# display_dvd_connectors.net
KiCad netlist of a schematic drawn in Altium Designer
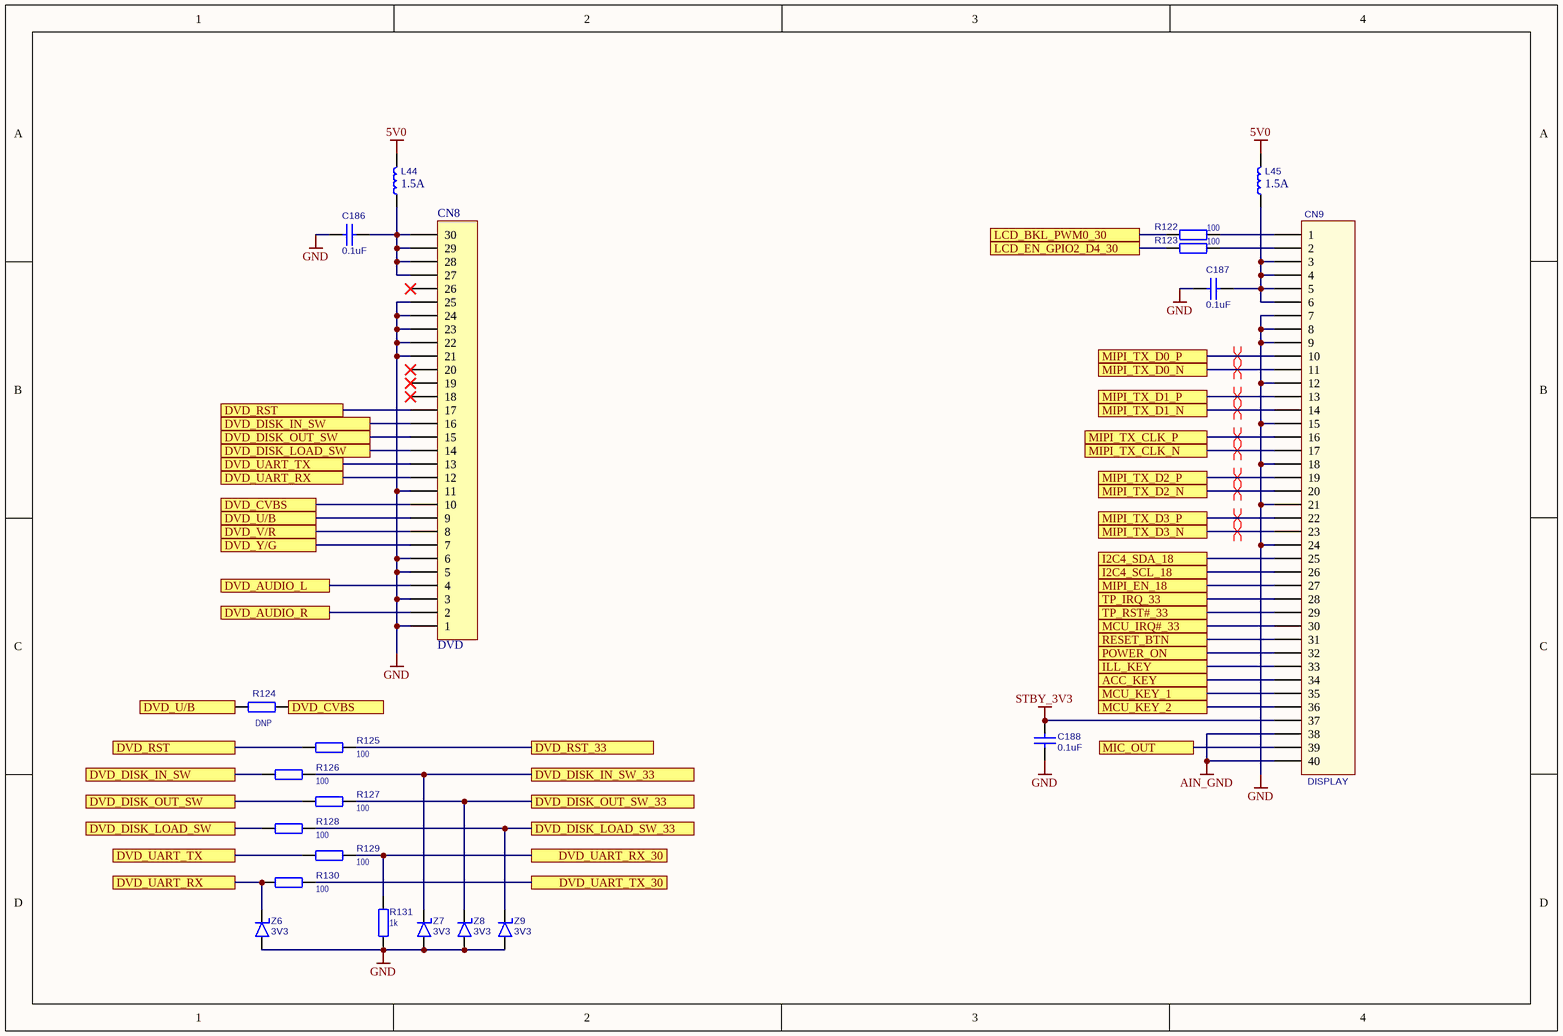
[diagram p0: display_dvd_connectors.SchDoc]

(export (version "E")
  (design (tool "Eeschema 10.0.6"))
  (components
    (comp (ref "C186")
      (value "0.1uF")
      (footprint "Capacitors:C0603")
      (description "CAP_NPOL")
      (fields (field (name "Comment") "C1608X7R1H104K080AA"))
      (libsource (lib "capacitors") (part "CAP_NPOL"))
    )
    (comp (ref "C187")
      (value "0.1uF")
      (footprint "Capacitors:C0603")
      (description "CAP_NPOL")
      (fields (field (name "Comment") "C1608X7R1H104K080AA"))
      (libsource (lib "capacitors") (part "CAP_NPOL"))
    )
    (comp (ref "C188")
      (value "0.1uF")
      (footprint "Capacitors:C0603")
      (description "CAP_NPOL")
      (fields (field (name "Comment") "C1608X7R1H104K080AA"))
      (libsource (lib "capacitors") (part "CAP_NPOL"))
    )
    (comp (ref "CN8")
      (value "DVD")
      (footprint "30S-0.5SH")
      (description "Header, 30-Pin")
      (fields (field (name "PUBLISHER") "Altium Limited"))
      (libsource (lib "HDR") (part "HDR 30"))
    )
    (comp (ref "CN9")
      (value "DISPLAY")
      (footprint "40S-0.5SH")
      (description "DT38")
      (libsource (lib "FPC_FH12-40S-0.5SH") (part "FH12-40"))
    )
    (comp (ref "L44")
      (value "1.5A")
      (footprint "IND1206")
      (description "IND_WO_IRON")
      (fields (field (name "Comment") "BLM31PG601SN1L"))
      (libsource (lib "inductors") (part "IND_WO_IRON"))
    )
    (comp (ref "L45")
      (value "1.5A")
      (footprint "IND1206")
      (description "IND_WO_IRON")
      (fields (field (name "Comment") "BLM31PG601SN1L"))
      (libsource (lib "inductors") (part "IND_WO_IRON"))
    )
    (comp (ref "R122")
      (value "100")
      (footprint "R0603")
      (description "RES")
      (libsource (lib "resistors") (part "RESISTOR"))
    )
    (comp (ref "R123")
      (value "100")
      (footprint "R0603")
      (description "RES")
      (libsource (lib "resistors") (part "RESISTOR"))
    )
    (comp (ref "R124")
      (value "DNP")
      (footprint "R0603")
      (description "RES")
      (libsource (lib "resistors") (part "RESISTOR"))
    )
    (comp (ref "R125")
      (value "100")
      (footprint "R0603")
      (description "RES")
      (libsource (lib "resistors") (part "RESISTOR"))
    )
    (comp (ref "R126")
      (value "100")
      (footprint "R0603")
      (description "RES")
      (libsource (lib "resistors") (part "RESISTOR"))
    )
    (comp (ref "R127")
      (value "100")
      (footprint "R0603")
      (description "RES")
      (libsource (lib "resistors") (part "RESISTOR"))
    )
    (comp (ref "R128")
      (value "100")
      (footprint "R0603")
      (description "RES")
      (libsource (lib "resistors") (part "RESISTOR"))
    )
    (comp (ref "R129")
      (value "100")
      (footprint "R0603")
      (description "RES")
      (libsource (lib "resistors") (part "RESISTOR"))
    )
    (comp (ref "R130")
      (value "100")
      (footprint "R0603")
      (description "RES")
      (libsource (lib "resistors") (part "RESISTOR"))
    )
    (comp (ref "R131")
      (value "1k")
      (footprint "R0603")
      (description "RES")
      (libsource (lib "resistors") (part "RESISTOR"))
    )
    (comp (ref "Z6")
      (value "3V3")
      (footprint "SOD-323")
      (description "ZENNER")
      (fields (field (name "Comment") "BZX384-C3V3.115"))
      (libsource (lib "diodes") (part "ZENNER_1"))
    )
    (comp (ref "Z7")
      (value "3V3")
      (footprint "SOD-323")
      (description "ZENNER")
      (fields (field (name "Comment") "BZX384-C3V3.115"))
      (libsource (lib "diodes") (part "ZENNER_1"))
    )
    (comp (ref "Z8")
      (value "3V3")
      (footprint "SOD-323")
      (description "ZENNER")
      (fields (field (name "Comment") "BZX384-C3V3.115"))
      (libsource (lib "diodes") (part "ZENNER_1"))
    )
    (comp (ref "Z9")
      (value "3V3")
      (footprint "SOD-323")
      (description "ZENNER")
      (fields (field (name "Comment") "BZX384-C3V3.115"))
      (libsource (lib "diodes") (part "ZENNER_1"))
    )
  )
  (nets
    (net (code "1") (name "/ACC_KEY") (class "Default")
      (node (ref "CN9") (pin "34") (pinfunction "34_34") (pintype "passive"))
    )
    (net (code "2") (name "/DVD_AUDIO_L") (class "Default")
      (node (ref "CN8") (pin "4") (pinfunction "4_4") (pintype "passive"))
    )
    (net (code "3") (name "/DVD_AUDIO_R") (class "Default")
      (node (ref "CN8") (pin "2") (pinfunction "2_2") (pintype "passive"))
    )
    (net (code "4") (name "/DVD_CVBS") (class "Default")
      (node (ref "CN8") (pin "10") (pinfunction "10_10") (pintype "passive"))
      (node (ref "R124") (pin "1") (pinfunction "1_1") (pintype "passive"))
    )
    (net (code "5") (name "/DVD_DISK_IN_SW") (class "Default")
      (node (ref "CN8") (pin "16") (pinfunction "16_16") (pintype "passive"))
      (node (ref "R126") (pin "2") (pinfunction "2_2") (pintype "passive"))
    )
    (net (code "6") (name "/DVD_DISK_IN_SW_33") (class "Default")
      (node (ref "R126") (pin "1") (pinfunction "1_1") (pintype "passive"))
      (node (ref "Z7") (pin "2") (pinfunction "K_2") (pintype "passive"))
    )
    (net (code "7") (name "/DVD_DISK_LOAD_SW") (class "Default")
      (node (ref "CN8") (pin "14") (pinfunction "14_14") (pintype "passive"))
      (node (ref "R128") (pin "2") (pinfunction "2_2") (pintype "passive"))
    )
    (net (code "8") (name "/DVD_DISK_LOAD_SW_33") (class "Default")
      (node (ref "R128") (pin "1") (pinfunction "1_1") (pintype "passive"))
      (node (ref "Z9") (pin "2") (pinfunction "K_2") (pintype "passive"))
    )
    (net (code "9") (name "/DVD_DISK_OUT_SW") (class "Default")
      (node (ref "CN8") (pin "15") (pinfunction "15_15") (pintype "passive"))
      (node (ref "R127") (pin "2") (pinfunction "2_2") (pintype "passive"))
    )
    (net (code "10") (name "/DVD_DISK_OUT_SW_33") (class "Default")
      (node (ref "R127") (pin "1") (pinfunction "1_1") (pintype "passive"))
      (node (ref "Z8") (pin "2") (pinfunction "K_2") (pintype "passive"))
    )
    (net (code "11") (name "/DVD_RST") (class "Default")
      (node (ref "CN8") (pin "17") (pinfunction "17_17") (pintype "passive"))
      (node (ref "R125") (pin "2") (pinfunction "2_2") (pintype "passive"))
    )
    (net (code "12") (name "/DVD_RST_33") (class "Default")
      (node (ref "R125") (pin "1") (pinfunction "1_1") (pintype "passive"))
    )
    (net (code "13") (name "/DVD_UART_RX") (class "Default")
      (node (ref "CN8") (pin "12") (pinfunction "12_12") (pintype "passive"))
      (node (ref "R130") (pin "2") (pinfunction "2_2") (pintype "passive"))
      (node (ref "Z6") (pin "2") (pinfunction "K_2") (pintype "passive"))
    )
    (net (code "14") (name "/DVD_UART_RX_30") (class "Default")
      (node (ref "R129") (pin "1") (pinfunction "1_1") (pintype "passive"))
      (node (ref "R131") (pin "1") (pinfunction "1_1") (pintype "passive"))
    )
    (net (code "15") (name "/DVD_UART_TX") (class "Default")
      (node (ref "CN8") (pin "13") (pinfunction "13_13") (pintype "passive"))
      (node (ref "R129") (pin "2") (pinfunction "2_2") (pintype "passive"))
    )
    (net (code "16") (name "/DVD_UART_TX_30") (class "Default")
      (node (ref "R130") (pin "1") (pinfunction "1_1") (pintype "passive"))
    )
    (net (code "17") (name "/DVD_U{slash}B") (class "Default")
      (node (ref "CN8") (pin "9") (pinfunction "9_9") (pintype "passive"))
      (node (ref "R124") (pin "2") (pinfunction "2_2") (pintype "passive"))
    )
    (net (code "18") (name "/DVD_V{slash}R") (class "Default")
      (node (ref "CN8") (pin "8") (pinfunction "8_8") (pintype "passive"))
    )
    (net (code "19") (name "/DVD_Y{slash}G") (class "Default")
      (node (ref "CN8") (pin "7") (pinfunction "7_7") (pintype "passive"))
    )
    (net (code "20") (name "/I2C4_SCL_18") (class "Default")
      (node (ref "CN9") (pin "26") (pinfunction "26_26") (pintype "passive"))
    )
    (net (code "21") (name "/I2C4_SDA_18") (class "Default")
      (node (ref "CN9") (pin "25") (pinfunction "25_25") (pintype "passive"))
    )
    (net (code "22") (name "/ILL_KEY") (class "Default")
      (node (ref "CN9") (pin "33") (pinfunction "33_33") (pintype "passive"))
    )
    (net (code "23") (name "/LCD_BKL_PWM0_30") (class "Default")
      (node (ref "R122") (pin "1") (pinfunction "1_1") (pintype "passive"))
    )
    (net (code "24") (name "/LCD_EN_GPIO2_D4_30") (class "Default")
      (node (ref "R123") (pin "1") (pinfunction "1_1") (pintype "passive"))
    )
    (net (code "25") (name "/MCU_IRQ#_33") (class "Default")
      (node (ref "CN9") (pin "30") (pinfunction "30_30") (pintype "passive"))
    )
    (net (code "26") (name "/MCU_KEY_1") (class "Default")
      (node (ref "CN9") (pin "35") (pinfunction "35_35") (pintype "passive"))
    )
    (net (code "27") (name "/MCU_KEY_2") (class "Default")
      (node (ref "CN9") (pin "36") (pinfunction "36_36") (pintype "passive"))
    )
    (net (code "28") (name "/MIC_OUT") (class "Default")
      (node (ref "CN9") (pin "39") (pinfunction "39_39") (pintype "passive"))
    )
    (net (code "29") (name "/MIPI_EN_18") (class "Default")
      (node (ref "CN9") (pin "27") (pinfunction "27_27") (pintype "passive"))
    )
    (net (code "30") (name "/MIPI_TX_CLK_N") (class "Default")
      (node (ref "CN9") (pin "17") (pinfunction "17_17") (pintype "passive"))
    )
    (net (code "31") (name "/MIPI_TX_CLK_P") (class "Default")
      (node (ref "CN9") (pin "16") (pinfunction "16_16") (pintype "passive"))
    )
    (net (code "32") (name "/MIPI_TX_D0_N") (class "Default")
      (node (ref "CN9") (pin "11") (pinfunction "11_11") (pintype "passive"))
    )
    (net (code "33") (name "/MIPI_TX_D0_P") (class "Default")
      (node (ref "CN9") (pin "10") (pinfunction "10_10") (pintype "passive"))
    )
    (net (code "34") (name "/MIPI_TX_D1_N") (class "Default")
      (node (ref "CN9") (pin "14") (pinfunction "14_14") (pintype "passive"))
    )
    (net (code "35") (name "/MIPI_TX_D1_P") (class "Default")
      (node (ref "CN9") (pin "13") (pinfunction "13_13") (pintype "passive"))
    )
    (net (code "36") (name "/MIPI_TX_D2_N") (class "Default")
      (node (ref "CN9") (pin "20") (pinfunction "20_20") (pintype "passive"))
    )
    (net (code "37") (name "/MIPI_TX_D2_P") (class "Default")
      (node (ref "CN9") (pin "19") (pinfunction "19_19") (pintype "passive"))
    )
    (net (code "38") (name "/MIPI_TX_D3_N") (class "Default")
      (node (ref "CN9") (pin "23") (pinfunction "23_23") (pintype "passive"))
    )
    (net (code "39") (name "/MIPI_TX_D3_P") (class "Default")
      (node (ref "CN9") (pin "22") (pinfunction "22_22") (pintype "passive"))
    )
    (net (code "40") (name "/POWER_ON") (class "Default")
      (node (ref "CN9") (pin "32") (pinfunction "32_32") (pintype "passive"))
    )
    (net (code "41") (name "/RESET_BTN") (class "Default")
      (node (ref "CN9") (pin "31") (pinfunction "31_31") (pintype "passive"))
    )
    (net (code "42") (name "/TP_IRQ_33") (class "Default")
      (node (ref "CN9") (pin "28") (pinfunction "28_28") (pintype "passive"))
    )
    (net (code "43") (name "/TP_RST#_33") (class "Default")
      (node (ref "CN9") (pin "29") (pinfunction "29_29") (pintype "passive"))
    )
    (net (code "44") (name "5V0") (class "Default")
      (node (ref "L44") (pin "2") (pintype "passive"))
      (node (ref "L45") (pin "2") (pintype "passive"))
    )
    (net (code "45") (name "AIN_GND") (class "Default")
      (node (ref "CN9") (pin "38") (pinfunction "38_38") (pintype "passive"))
      (node (ref "CN9") (pin "40") (pinfunction "40_40") (pintype "passive"))
    )
    (net (code "46") (name "GND") (class "Default")
      (node (ref "C186") (pin "1") (pinfunction "1_1") (pintype "passive"))
      (node (ref "C187") (pin "1") (pinfunction "1_1") (pintype "passive"))
      (node (ref "C188") (pin "1") (pinfunction "1_1") (pintype "passive"))
      (node (ref "CN8") (pin "1") (pinfunction "1_1") (pintype "passive"))
      (node (ref "CN8") (pin "11") (pinfunction "11_11") (pintype "passive"))
      (node (ref "CN8") (pin "21") (pinfunction "21_21") (pintype "passive"))
      (node (ref "CN8") (pin "22") (pinfunction "22_22") (pintype "passive"))
      (node (ref "CN8") (pin "23") (pinfunction "23_23") (pintype "passive"))
      (node (ref "CN8") (pin "24") (pinfunction "24_24") (pintype "passive"))
      (node (ref "CN8") (pin "25") (pinfunction "25_25") (pintype "passive"))
      (node (ref "CN8") (pin "3") (pinfunction "3_3") (pintype "passive"))
      (node (ref "CN8") (pin "5") (pinfunction "5_5") (pintype "passive"))
      (node (ref "CN8") (pin "6") (pinfunction "6_6") (pintype "passive"))
      (node (ref "CN9") (pin "12") (pinfunction "12_12") (pintype "passive"))
      (node (ref "CN9") (pin "15") (pinfunction "15_15") (pintype "passive"))
      (node (ref "CN9") (pin "18") (pinfunction "18_18") (pintype "passive"))
      (node (ref "CN9") (pin "21") (pinfunction "21_21") (pintype "passive"))
      (node (ref "CN9") (pin "24") (pinfunction "24_24") (pintype "passive"))
      (node (ref "CN9") (pin "7") (pinfunction "7_7") (pintype "passive"))
      (node (ref "CN9") (pin "8") (pinfunction "8_8") (pintype "passive"))
      (node (ref "CN9") (pin "9") (pinfunction "9_9") (pintype "passive"))
      (node (ref "R131") (pin "2") (pinfunction "2_2") (pintype "passive"))
      (node (ref "Z6") (pin "1") (pinfunction "A_1") (pintype "passive"))
      (node (ref "Z7") (pin "1") (pinfunction "A_1") (pintype "passive"))
      (node (ref "Z8") (pin "1") (pinfunction "A_1") (pintype "passive"))
      (node (ref "Z9") (pin "1") (pinfunction "A_1") (pintype "passive"))
    )
    (net (code "47") (name "Net-(C186-Pad2)") (class "Default")
      (node (ref "C186") (pin "2") (pinfunction "2_2") (pintype "passive"))
      (node (ref "CN8") (pin "27") (pinfunction "27_27") (pintype "passive"))
      (node (ref "CN8") (pin "28") (pinfunction "28_28") (pintype "passive"))
      (node (ref "CN8") (pin "29") (pinfunction "29_29") (pintype "passive"))
      (node (ref "CN8") (pin "30") (pinfunction "30_30") (pintype "passive"))
      (node (ref "L44") (pin "1") (pintype "passive"))
    )
    (net (code "48") (name "Net-(C187-Pad2)") (class "Default")
      (node (ref "C187") (pin "2") (pinfunction "2_2") (pintype "passive"))
      (node (ref "CN9") (pin "3") (pinfunction "3_3") (pintype "passive"))
      (node (ref "CN9") (pin "4") (pinfunction "4_4") (pintype "passive"))
      (node (ref "CN9") (pin "5") (pinfunction "5_5") (pintype "passive"))
      (node (ref "CN9") (pin "6") (pinfunction "6_6") (pintype "passive"))
      (node (ref "L45") (pin "1") (pintype "passive"))
    )
    (net (code "49") (name "Net-(CN9-Pad1)") (class "Default")
      (node (ref "CN9") (pin "1") (pinfunction "1_1") (pintype "passive"))
      (node (ref "R122") (pin "2") (pinfunction "2_2") (pintype "passive"))
    )
    (net (code "50") (name "Net-(CN9-Pad2)") (class "Default")
      (node (ref "CN9") (pin "2") (pinfunction "2_2") (pintype "passive"))
      (node (ref "R123") (pin "2") (pinfunction "2_2") (pintype "passive"))
    )
    (net (code "51") (name "STBY_3V3") (class "Default")
      (node (ref "C188") (pin "2") (pinfunction "2_2") (pintype "passive"))
      (node (ref "CN9") (pin "37") (pinfunction "37_37") (pintype "passive"))
    )
    (net (code "52") (name "unconnected-(CN8-Pad18)") (class "Default")
      (node (ref "CN8") (pin "18") (pinfunction "18_18") (pintype "passive+no_connect"))
    )
    (net (code "53") (name "unconnected-(CN8-Pad19)") (class "Default")
      (node (ref "CN8") (pin "19") (pinfunction "19_19") (pintype "passive+no_connect"))
    )
    (net (code "54") (name "unconnected-(CN8-Pad20)") (class "Default")
      (node (ref "CN8") (pin "20") (pinfunction "20_20") (pintype "passive+no_connect"))
    )
    (net (code "55") (name "unconnected-(CN8-Pad26)") (class "Default")
      (node (ref "CN8") (pin "26") (pinfunction "26_26") (pintype "passive+no_connect"))
    )
  )
)
